# SCH.net
KiCad netlist of a schematic drawn in EasyEDA
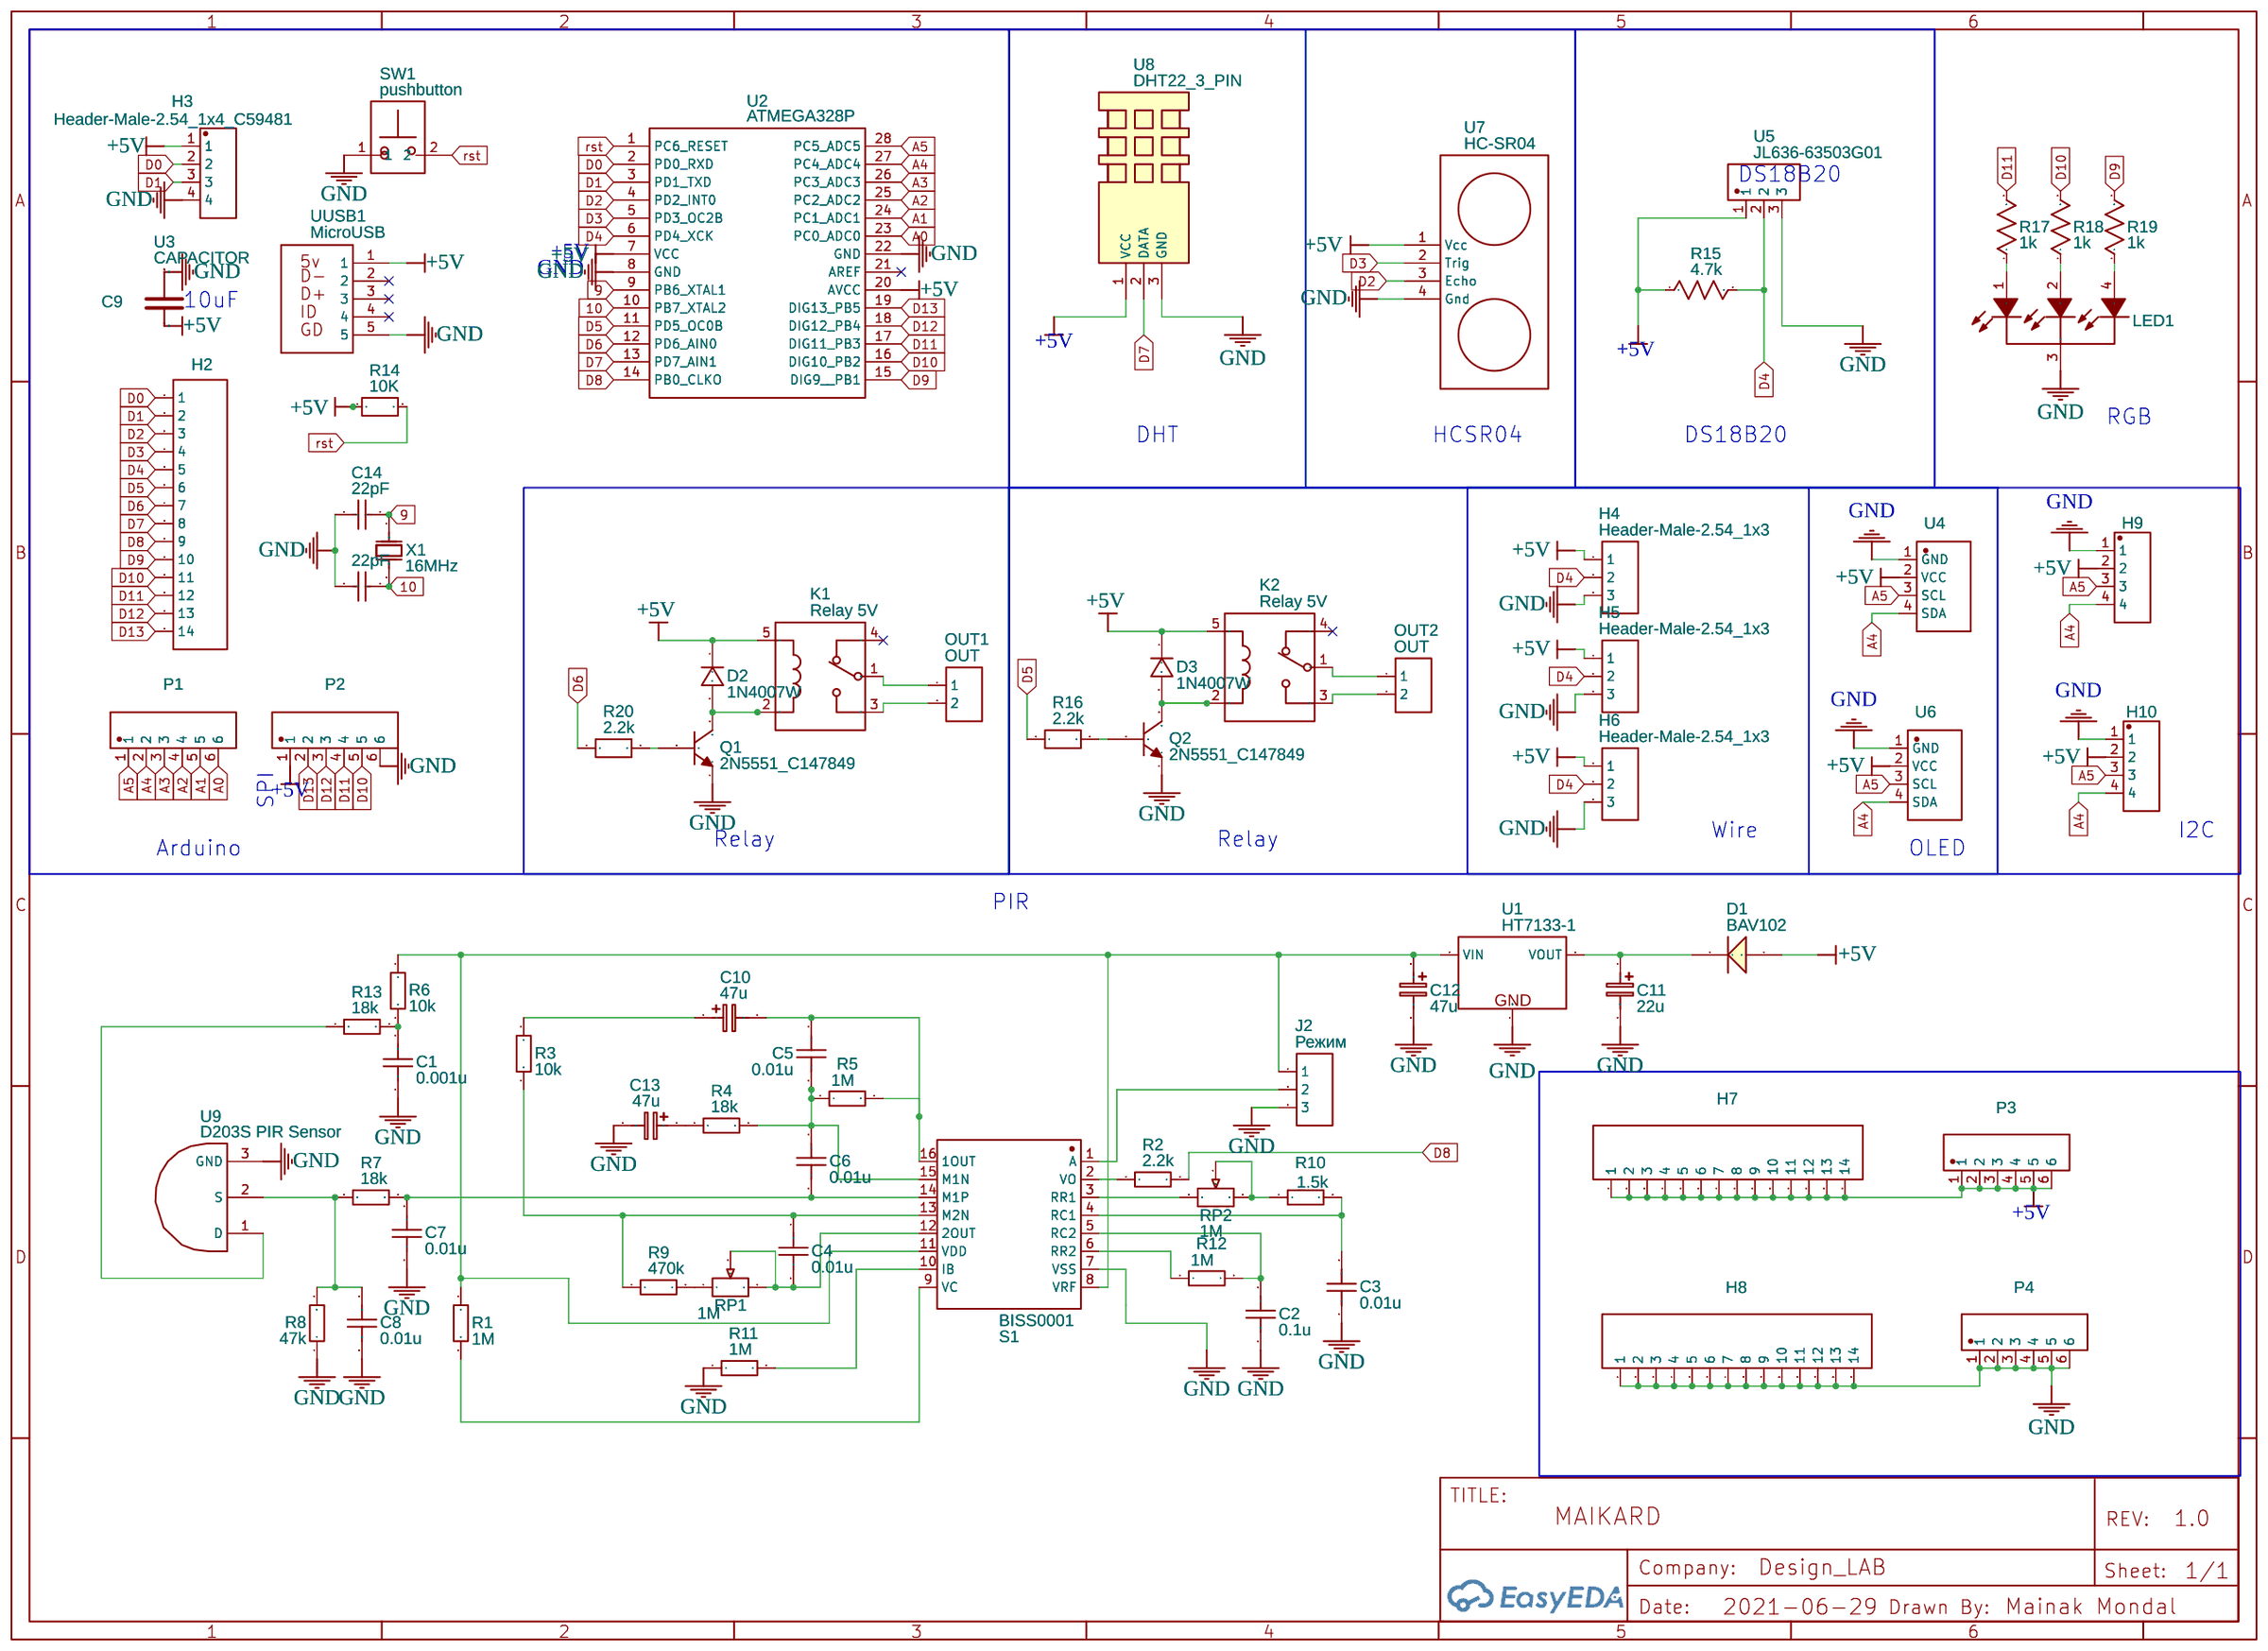
[diagram p0: schematic sheet]

(export (version "E")
  (design (tool "Eeschema 10.0.6"))
  (components
    (comp (ref "C1") (value "0.001u") (libsource (lib "") (part "C_0603_US")))
    (comp (ref "C2") (value "0.1u") (libsource (lib "") (part "C_0603_US_2")))
    (comp (ref "C3") (value "0.01u") (libsource (lib "") (part "C_0603_US")))
    (comp (ref "C4") (value "0.01u") (libsource (lib "") (part "C_0603_US_2")))
    (comp (ref "C5") (value "0.01u") (libsource (lib "") (part "C_0603_US_1")))
    (comp (ref "C6") (value "0.01u") (libsource (lib "") (part "C_0603_US_2")))
    (comp (ref "C7") (value "0.01u") (libsource (lib "") (part "C_0603_US")))
    (comp (ref "C8") (value "0.01u") (libsource (lib "") (part "C_0603_US_2")))
    (comp (ref "C9")
      (value "22pF")
      (fields
        (field (name "BOM_Manufacturer Part") "22pf/50V 10%")
        (field (name "BOM_Supplier Part") "C9316")
      )
      (libsource (lib "") (part "22pF"))
    )
    (comp (ref "C10") (value "47u") (libsource (lib "") (part "CE_TH_D3.0×F1.5_EU")))
    (comp (ref "C11") (value "22u") (libsource (lib "") (part "CE_TH_D3.0×F1.5_EU_2")))
    (comp (ref "C12") (value "47u") (libsource (lib "") (part "CE_TH_D3.0×F1.5_EU_3")))
    (comp (ref "C13") (value "47u") (libsource (lib "") (part "CE_TH_D3.0×F1.5_EU_1")))
    (comp (ref "C14")
      (value "22pF")
      (fields
        (field (name "BOM_Manufacturer Part") "22pf/50V 10%")
        (field (name "BOM_Supplier Part") "C9316")
      )
      (libsource (lib "") (part "22pF"))
    )
    (comp (ref "D1") (value "BAV102") (libsource (lib "") (part "BAV102")))
    (comp (ref "D2")
      (value "1N4007W")
      (fields (field (name "BOM_Supplier Part") "C328592"))
      (libsource (lib "") (part "1N4007W"))
    )
    (comp (ref "D3")
      (value "1N4007W")
      (fields (field (name "BOM_Supplier Part") "C328592"))
      (libsource (lib "") (part "1N4007W"))
    )
    (comp (ref "H2")
      (value "Female header 2.54-1*14P")
      (fields (field (name "BOM_Supplier Part") "C52711"))
      (libsource (lib "") (part "Female header 2.54-1*14P"))
    )
    (comp (ref "H3")
      (value "Header-Male-2.54_1x4_C59481")
      (fields
        (field (name "BOM_Manufacturer Part") "Headers  Pins 1*4P")
        (field (name "BOM_Supplier Part") "C59481")
      )
      (libsource (lib "") (part "Header-Male-2.54_1x4_C59481"))
    )
    (comp (ref "H4")
      (value "Header-Male-2.54_1x3")
      (fields
        (field (name "BOM_Manufacturer Part") "Header2.54mm 1*3P")
        (field (name "BOM_Supplier Part") "C49257")
      )
      (libsource (lib "") (part "Header-Male-2.54_1x3"))
    )
    (comp (ref "H5")
      (value "Header-Male-2.54_1x3")
      (fields
        (field (name "BOM_Manufacturer Part") "Header2.54mm 1*3P")
        (field (name "BOM_Supplier Part") "C49257")
      )
      (libsource (lib "") (part "Header-Male-2.54_1x3"))
    )
    (comp (ref "H6")
      (value "Header-Male-2.54_1x3")
      (fields
        (field (name "BOM_Manufacturer Part") "Header2.54mm 1*3P")
        (field (name "BOM_Supplier Part") "C49257")
      )
      (libsource (lib "") (part "Header-Male-2.54_1x3"))
    )
    (comp (ref "H7")
      (value "Female header 2.54-1*14P")
      (fields (field (name "BOM_Supplier Part") "C52711"))
      (libsource (lib "") (part "Female header 2.54-1*14P_1"))
    )
    (comp (ref "H8")
      (value "Female header 2.54-1*14P")
      (fields (field (name "BOM_Supplier Part") "C52711"))
      (libsource (lib "") (part "Female header 2.54-1*14P_1"))
    )
    (comp (ref "H9")
      (value "Header-Male-2.54_1x4_C59481")
      (fields
        (field (name "BOM_Manufacturer Part") "Headers  Pins 1*4P")
        (field (name "BOM_Supplier Part") "C59481")
      )
      (libsource (lib "") (part "Header-Male-2.54_1x4_C59481"))
    )
    (comp (ref "H10")
      (value "Header-Male-2.54_1x4_C59481")
      (fields
        (field (name "BOM_Manufacturer Part") "Headers  Pins 1*4P")
        (field (name "BOM_Supplier Part") "C59481")
      )
      (libsource (lib "") (part "Header-Male-2.54_1x4_C59481"))
    )
    (comp (ref "J2")
      (value "Режим")
      (fields (field (name "BOM_Supplier Part") "C180248"))
      (libsource (lib "") (part "HDR-M-2.54_1x3"))
    )
    (comp (ref "K1")
      (value "Relay 5V")
      (fields
        (field (name "BOM_Manufacturer Part") "RelayHT3F-12VDC-SHG")
        (field (name "BOM_Supplier Part") "C22022")
      )
      (libsource (lib "") (part "RelayHT3F-12VDC-SHG"))
    )
    (comp (ref "K2")
      (value "Relay 5V")
      (fields
        (field (name "BOM_Manufacturer Part") "RelayHT3F-12VDC-SHG")
        (field (name "BOM_Supplier Part") "C22022")
      )
      (libsource (lib "") (part "RelayHT3F-12VDC-SHG"))
    )
    (comp (ref "LED1")
      (value "RGB LED Common Cathode DIP Package")
      (fields
        (field (name "BOM_Manufacturer Part") "φ5 RGB Transparent LED")
        (field (name "BOM_Supplier Part") "C32985")
      )
      (libsource (lib "") (part "RGB LED Common Cathode DIP Package"))
    )
    (comp (ref "OUT1")
      (value "OUT")
      (fields (field (name "BOM_Supplier Part") "C124375"))
      (libsource (lib "") (part "HDR-M-2.54_1x2"))
    )
    (comp (ref "OUT2")
      (value "OUT")
      (fields (field (name "BOM_Supplier Part") "C124375"))
      (libsource (lib "") (part "HDR-M-2.54_1x2"))
    )
    (comp (ref "P1")
      (value "Header-Female-2.54_1x6")
      (fields
        (field (name "BOM_Manufacturer Part") "Female header 1*6p")
        (field (name "BOM_Supplier Part") "C40877")
      )
      (libsource (lib "") (part "Header-Female-2.54_1x6"))
    )
    (comp (ref "P2")
      (value "Header-Female-2.54_1x6")
      (fields
        (field (name "BOM_Manufacturer Part") "Female header 1*6p")
        (field (name "BOM_Supplier Part") "C40877")
      )
      (libsource (lib "") (part "Header-Female-2.54_1x6"))
    )
    (comp (ref "P3")
      (value "Header-Female-2.54_1x6")
      (fields
        (field (name "BOM_Manufacturer Part") "Female header 1*6p")
        (field (name "BOM_Supplier Part") "C40877")
      )
      (libsource (lib "") (part "Header-Female-2.54_1x6"))
    )
    (comp (ref "P4")
      (value "Header-Female-2.54_1x6")
      (fields
        (field (name "BOM_Manufacturer Part") "Female header 1*6p")
        (field (name "BOM_Supplier Part") "C40877")
      )
      (libsource (lib "") (part "Header-Female-2.54_1x6"))
    )
    (comp (ref "Q1")
      (value "2N5551_C147849")
      (fields (field (name "BOM_Manufacturer Part") "2N5551") (field (name "BOM_Supplier Part") "C147849"))
      (libsource (lib "") (part "2N5551_C147849"))
    )
    (comp (ref "Q2")
      (value "2N5551_C147849")
      (fields (field (name "BOM_Manufacturer Part") "2N5551") (field (name "BOM_Supplier Part") "C147849"))
      (libsource (lib "") (part "2N5551_C147849"))
    )
    (comp (ref "R1")
      (value "1M")
      (fields
        (field (name "BOM_Manufacturer Part") "0.56R(R56) ±1%")
        (field (name "BOM_Supplier Part") "C19772")
      )
      (libsource (lib "") (part "0.56Ω_1"))
    )
    (comp (ref "R2")
      (value "2.2k")
      (fields
        (field (name "BOM_Manufacturer Part") "0.56R(R56) ±1%")
        (field (name "BOM_Supplier Part") "C19772")
      )
      (libsource (lib "") (part "0.56Ω"))
    )
    (comp (ref "R3")
      (value "10k")
      (fields
        (field (name "BOM_Manufacturer Part") "0.56R(R56) ±1%")
        (field (name "BOM_Supplier Part") "C19772")
      )
      (libsource (lib "") (part "0.56Ω_1"))
    )
    (comp (ref "R4")
      (value "18k")
      (fields
        (field (name "BOM_Manufacturer Part") "0.56R(R56) ±1%")
        (field (name "BOM_Supplier Part") "C19772")
      )
      (libsource (lib "") (part "0.56Ω"))
    )
    (comp (ref "R5")
      (value "1M")
      (fields
        (field (name "BOM_Manufacturer Part") "0.56R(R56) ±1%")
        (field (name "BOM_Supplier Part") "C19772")
      )
      (libsource (lib "") (part "0.56Ω"))
    )
    (comp (ref "R6")
      (value "10k")
      (fields
        (field (name "BOM_Manufacturer Part") "0.56R(R56) ±1%")
        (field (name "BOM_Supplier Part") "C19772")
      )
      (libsource (lib "") (part "0.56Ω_1"))
    )
    (comp (ref "R7")
      (value "18k")
      (fields
        (field (name "BOM_Manufacturer Part") "0.56R(R56) ±1%")
        (field (name "BOM_Supplier Part") "C19772")
      )
      (libsource (lib "") (part "0.56Ω"))
    )
    (comp (ref "R8")
      (value "47k")
      (fields
        (field (name "BOM_Manufacturer Part") "0.56R(R56) ±1%")
        (field (name "BOM_Supplier Part") "C19772")
      )
      (libsource (lib "") (part "0.56Ω_2"))
    )
    (comp (ref "R9")
      (value "470k")
      (fields
        (field (name "BOM_Manufacturer Part") "0.56R(R56) ±1%")
        (field (name "BOM_Supplier Part") "C19772")
      )
      (libsource (lib "") (part "0.56Ω"))
    )
    (comp (ref "R10")
      (value "1.5k")
      (fields
        (field (name "BOM_Manufacturer Part") "0.56R(R56) ±1%")
        (field (name "BOM_Supplier Part") "C19772")
      )
      (libsource (lib "") (part "0.56Ω"))
    )
    (comp (ref "R11")
      (value "1M")
      (fields
        (field (name "BOM_Manufacturer Part") "0.56R(R56) ±1%")
        (field (name "BOM_Supplier Part") "C19772")
      )
      (libsource (lib "") (part "0.56Ω"))
    )
    (comp (ref "R12")
      (value "1M")
      (fields
        (field (name "BOM_Manufacturer Part") "0.56R(R56) ±1%")
        (field (name "BOM_Supplier Part") "C19772")
      )
      (libsource (lib "") (part "0.56Ω"))
    )
    (comp (ref "R13")
      (value "18k")
      (fields
        (field (name "BOM_Manufacturer Part") "0.56R(R56) ±1%")
        (field (name "BOM_Supplier Part") "C19772")
      )
      (libsource (lib "") (part "0.56Ω"))
    )
    (comp (ref "R14")
      (value "10K")
      (fields
        (field (name "BOM_Manufacturer Part") "Resistor MF25 10K, 0.25W")
        (field (name "BOM_Supplier Part") "934-1110")
      )
      (libsource (lib "") (part "10K"))
    )
    (comp (ref "R15") (value "4.7k") (libsource (lib "") (part "R_0201_US")))
    (comp (ref "R16") (value "2.2k") (libsource (lib "") (part "R_AXIAL-0.3_EU")))
    (comp (ref "R17") (value "1k") (libsource (lib "") (part "R_0201_US_1")))
    (comp (ref "R18") (value "1k") (libsource (lib "") (part "R_0201_US_1")))
    (comp (ref "R19") (value "1k") (libsource (lib "") (part "R_0201_US_1")))
    (comp (ref "R20") (value "2.2k") (libsource (lib "") (part "R_AXIAL-0.3_EU")))
    (comp (ref "RP1") (value "1M") (libsource (lib "") (part "R_3386P_EU")))
    (comp (ref "RP2") (value "1M") (libsource (lib "") (part "R_3386P_EU")))
    (comp (ref "S1")
      (value "BISS0001")
      (fields (field (name "BOM_Supplier Part") "C82210"))
      (libsource (lib "") (part "BISS0001"))
    )
    (comp (ref "SW1") (value "pushbutton") (libsource (lib "") (part "pushbutton")))
    (comp (ref "U1")
      (value "HT7133-1")
      (fields (field (name "BOM_Supplier Part") "C347181"))
      (libsource (lib "") (part "HT7133-1"))
    )
    (comp (ref "U2")
      (value "ATMEGA328P")
      (fields
        (field (name "BOM_Manufacturer Part") "ATMEGA328P-PU")
        (field (name "BOM_Supplier Part") "C33901")
      )
      (libsource (lib "") (part "ATMEGA328P"))
    )
    (comp (ref "U3") (value "CAPACITOR") (libsource (lib "") (part "CAPACITOR")))
    (comp (ref "U4")
      (value "0.96 128X64 I2C SSD1306 OLED WHITE/BLUE")
      (fields (field (name "BOM_Manufacturer Part") "OLED 4PIN"))
      (libsource (lib "") (part "0.96 128X64 I2C SSD1306 OLED WHITE/BLUE"))
    )
    (comp (ref "U5")
      (value "JL636-63503G01")
      (fields (field (name "BOM_Supplier Part") "C394553"))
      (libsource (lib "") (part "JL636-63503G01"))
    )
    (comp (ref "U6")
      (value "0.96 128X64 I2C SSD1306 OLED WHITE/BLUE")
      (fields (field (name "BOM_Manufacturer Part") "OLED 4PIN"))
      (libsource (lib "") (part "0.96 128X64 I2C SSD1306 OLED WHITE/BLUE"))
    )
    (comp (ref "U7") (value "HC-SR04") (libsource (lib "") (part "HC-SR04")))
    (comp (ref "U8")
      (value "DHT22_3_PIN")
      (fields
        (field (name "BOM_Manufacturer Part") "DHT22")
        (field (name "BOM_Supplier Part") "PRODUCT ID: 385")
      )
      (libsource (lib "") (part "DHT22_3_PIN"))
    )
    (comp (ref "U9")
      (value "D203S PIR Sensor")
      (fields (field (name "BOM_Manufacturer Part") "D203S") (field (name "BOM_Supplier Part") "C78793"))
      (libsource (lib "") (part "D203S PIR Sensor"))
    )
    (comp (ref "UUSB1")
      (value "MicroUSB")
      (fields (field (name "BOM_Manufacturer Part") "Speaker"))
      (libsource (lib "") (part "MicroUSB"))
    )
    (comp (ref "X1")
      (value "16MHz")
      (fields
        (field (name "BOM_Manufacturer Part") "X49SD16MSD2SC")
        (field (name "BOM_Supplier Part") "C16212")
      )
      (libsource (lib "") (part "XTAL16MHZ DIP"))
    )
  )
  (nets
    (net (code "1") (name "+5V") (class "Default")
      (node (ref "D1") (pin "1") (pinfunction "A_1") (pintype "unspecified"))
      (node (ref "D2") (pin "1") (pinfunction "1_1") (pintype "unspecified"))
      (node (ref "D3") (pin "1") (pinfunction "1_1") (pintype "unspecified"))
      (node (ref "H10") (pin "2") (pinfunction "2_2") (pintype "unspecified"))
      (node (ref "H3") (pin "1") (pinfunction "1_1") (pintype "unspecified"))
      (node (ref "H4") (pin "1") (pinfunction "1_1") (pintype "input"))
      (node (ref "H5") (pin "1") (pinfunction "1_1") (pintype "input"))
      (node (ref "H6") (pin "1") (pinfunction "1_1") (pintype "input"))
      (node (ref "H7") (pin "1") (pinfunction "1_1") (pintype "input"))
      (node (ref "H7") (pin "10") (pinfunction "10_10") (pintype "input"))
      (node (ref "H7") (pin "11") (pinfunction "11_11") (pintype "input"))
      (node (ref "H7") (pin "12") (pinfunction "12_12") (pintype "input"))
      (node (ref "H7") (pin "13") (pinfunction "13_13") (pintype "input"))
      (node (ref "H7") (pin "14") (pinfunction "14_14") (pintype "input"))
      (node (ref "H7") (pin "2") (pinfunction "2_2") (pintype "input"))
      (node (ref "H7") (pin "3") (pinfunction "3_3") (pintype "input"))
      (node (ref "H7") (pin "4") (pinfunction "4_4") (pintype "input"))
      (node (ref "H7") (pin "5") (pinfunction "5_5") (pintype "input"))
      (node (ref "H7") (pin "6") (pinfunction "6_6") (pintype "input"))
      (node (ref "H7") (pin "7") (pinfunction "7_7") (pintype "input"))
      (node (ref "H7") (pin "8") (pinfunction "8_8") (pintype "input"))
      (node (ref "H7") (pin "9") (pinfunction "9_9") (pintype "input"))
      (node (ref "H9") (pin "2") (pinfunction "2_2") (pintype "unspecified"))
      (node (ref "K1") (pin "5") (pinfunction "5_5") (pintype "unspecified"))
      (node (ref "K2") (pin "5") (pinfunction "5_5") (pintype "unspecified"))
      (node (ref "P2") (pin "1") (pinfunction "1_1") (pintype "unspecified"))
      (node (ref "P3") (pin "1") (pinfunction "1_1") (pintype "unspecified"))
      (node (ref "P3") (pin "2") (pinfunction "2_2") (pintype "unspecified"))
      (node (ref "P3") (pin "3") (pinfunction "3_3") (pintype "unspecified"))
      (node (ref "P3") (pin "4") (pinfunction "4_4") (pintype "unspecified"))
      (node (ref "P3") (pin "5") (pinfunction "5_5") (pintype "unspecified"))
      (node (ref "P3") (pin "6") (pinfunction "6_6") (pintype "unspecified"))
      (node (ref "R14") (pin "1") (pinfunction "1_1") (pintype "unspecified"))
      (node (ref "R15") (pin "1") (pinfunction "1_1") (pintype "unspecified"))
      (node (ref "U2") (pin "20") (pinfunction "AVCC_20") (pintype "passive"))
      (node (ref "U2") (pin "7") (pinfunction "VCC_7") (pintype "passive"))
      (node (ref "U3") (pin "P$1") (pinfunction "P$1_P$1") (pintype "unspecified"))
      (node (ref "U4") (pin "2") (pinfunction "VCC_2") (pintype "unspecified"))
      (node (ref "U5") (pin "1") (pinfunction "1_1") (pintype "unspecified"))
      (node (ref "U6") (pin "2") (pinfunction "VCC_2") (pintype "unspecified"))
      (node (ref "U7") (pin "1") (pinfunction "Vcc_1") (pintype "unspecified"))
      (node (ref "U8") (pin "1") (pinfunction "VCC_1") (pintype "unspecified"))
      (node (ref "UUSB1") (pin "1") (pinfunction "1_1") (pintype "unspecified"))
    )
    (net (code "2") (name "9") (class "Default")
      (node (ref "C14") (pin "2") (pinfunction "2_2") (pintype "input"))
      (node (ref "U2") (pin "9") (pinfunction "PB6_XTAL1_9") (pintype "bidirectional"))
      (node (ref "X1") (pin "1") (pinfunction "OSC1_1") (pintype "input"))
    )
    (net (code "3") (name "10") (class "Default")
      (node (ref "C9") (pin "2") (pinfunction "2_2") (pintype "input"))
      (node (ref "U2") (pin "10") (pinfunction "PB7_XTAL2_10") (pintype "bidirectional"))
      (node (ref "X1") (pin "2") (pinfunction "OSC2_2") (pintype "input"))
    )
    (net (code "4") (name "A0") (class "Default")
      (node (ref "P1") (pin "6") (pinfunction "6_6") (pintype "unspecified"))
      (node (ref "U2") (pin "23") (pinfunction "PC0_ADC0_23") (pintype "bidirectional"))
    )
    (net (code "5") (name "A1") (class "Default")
      (node (ref "P1") (pin "5") (pinfunction "5_5") (pintype "unspecified"))
      (node (ref "U2") (pin "24") (pinfunction "PC1_ADC1_24") (pintype "bidirectional"))
    )
    (net (code "6") (name "A2") (class "Default")
      (node (ref "P1") (pin "4") (pinfunction "4_4") (pintype "unspecified"))
      (node (ref "U2") (pin "25") (pinfunction "PC2_ADC2_25") (pintype "bidirectional"))
    )
    (net (code "7") (name "A3") (class "Default")
      (node (ref "P1") (pin "3") (pinfunction "3_3") (pintype "unspecified"))
      (node (ref "U2") (pin "26") (pinfunction "PC3_ADC3_26") (pintype "bidirectional"))
    )
    (net (code "8") (name "A4") (class "Default")
      (node (ref "H10") (pin "4") (pinfunction "4_4") (pintype "unspecified"))
      (node (ref "H9") (pin "4") (pinfunction "4_4") (pintype "unspecified"))
      (node (ref "P1") (pin "2") (pinfunction "2_2") (pintype "unspecified"))
      (node (ref "U2") (pin "27") (pinfunction "PC4_ADC4_27") (pintype "bidirectional"))
      (node (ref "U4") (pin "4") (pinfunction "SDA_4") (pintype "unspecified"))
      (node (ref "U6") (pin "4") (pinfunction "SDA_4") (pintype "unspecified"))
    )
    (net (code "9") (name "A5") (class "Default")
      (node (ref "H10") (pin "3") (pinfunction "3_3") (pintype "unspecified"))
      (node (ref "H9") (pin "3") (pinfunction "3_3") (pintype "unspecified"))
      (node (ref "P1") (pin "1") (pinfunction "1_1") (pintype "unspecified"))
      (node (ref "U2") (pin "28") (pinfunction "PC5_ADC5_28") (pintype "bidirectional"))
      (node (ref "U4") (pin "3") (pinfunction "SCL_3") (pintype "unspecified"))
      (node (ref "U6") (pin "3") (pinfunction "SCL_3") (pintype "unspecified"))
    )
    (net (code "10") (name "D0") (class "Default")
      (node (ref "H2") (pin "1") (pinfunction "1_1") (pintype "input"))
      (node (ref "H3") (pin "2") (pinfunction "2_2") (pintype "unspecified"))
      (node (ref "U2") (pin "2") (pinfunction "PD0_RXD_2") (pintype "bidirectional"))
    )
    (net (code "11") (name "D1") (class "Default")
      (node (ref "H2") (pin "2") (pinfunction "2_2") (pintype "input"))
      (node (ref "H3") (pin "3") (pinfunction "3_3") (pintype "unspecified"))
      (node (ref "U2") (pin "3") (pinfunction "PD1_TXD_3") (pintype "bidirectional"))
    )
    (net (code "12") (name "D2") (class "Default")
      (node (ref "H2") (pin "3") (pinfunction "3_3") (pintype "input"))
      (node (ref "U2") (pin "4") (pinfunction "PD2_INT0_4") (pintype "bidirectional"))
      (node (ref "U7") (pin "3") (pinfunction "Echo_3") (pintype "unspecified"))
    )
    (net (code "13") (name "D3") (class "Default")
      (node (ref "H2") (pin "4") (pinfunction "4_4") (pintype "input"))
      (node (ref "U2") (pin "5") (pinfunction "PD3_OC2B_5") (pintype "bidirectional"))
      (node (ref "U7") (pin "2") (pinfunction "Trig_2") (pintype "unspecified"))
    )
    (net (code "14") (name "D4") (class "Default")
      (node (ref "H2") (pin "5") (pinfunction "5_5") (pintype "input"))
      (node (ref "H4") (pin "2") (pinfunction "2_2") (pintype "input"))
      (node (ref "H5") (pin "2") (pinfunction "2_2") (pintype "input"))
      (node (ref "H6") (pin "2") (pinfunction "2_2") (pintype "input"))
      (node (ref "R15") (pin "2") (pinfunction "2_2") (pintype "unspecified"))
      (node (ref "U2") (pin "6") (pinfunction "PD4_XCK_6") (pintype "bidirectional"))
      (node (ref "U5") (pin "2") (pinfunction "2_2") (pintype "unspecified"))
    )
    (net (code "15") (name "D5") (class "Default")
      (node (ref "H2") (pin "6") (pinfunction "6_6") (pintype "input"))
      (node (ref "R16") (pin "1") (pinfunction "1_1") (pintype "unspecified"))
      (node (ref "U2") (pin "11") (pinfunction "PD5_OC0B_11") (pintype "bidirectional"))
    )
    (net (code "16") (name "D6") (class "Default")
      (node (ref "H2") (pin "7") (pinfunction "7_7") (pintype "input"))
      (node (ref "R20") (pin "1") (pinfunction "1_1") (pintype "unspecified"))
      (node (ref "U2") (pin "12") (pinfunction "PD6_AIN0_12") (pintype "bidirectional"))
    )
    (net (code "17") (name "D7") (class "Default")
      (node (ref "H2") (pin "8") (pinfunction "8_8") (pintype "input"))
      (node (ref "U2") (pin "13") (pinfunction "PD7_AIN1_13") (pintype "bidirectional"))
      (node (ref "U8") (pin "2") (pinfunction "DATA_2") (pintype "unspecified"))
    )
    (net (code "18") (name "D8") (class "Default")
      (node (ref "H2") (pin "9") (pinfunction "9_9") (pintype "input"))
      (node (ref "R2") (pin "2") (pinfunction "2_2") (pintype "input"))
      (node (ref "U2") (pin "14") (pinfunction "PB0_CLKO_14") (pintype "bidirectional"))
    )
    (net (code "19") (name "D9") (class "Default")
      (node (ref "H2") (pin "10") (pinfunction "10_10") (pintype "input"))
      (node (ref "R19") (pin "2") (pinfunction "2_2") (pintype "unspecified"))
      (node (ref "U2") (pin "15") (pinfunction "DIG9__PB1_15") (pintype "bidirectional"))
    )
    (net (code "20") (name "D10") (class "Default")
      (node (ref "H2") (pin "11") (pinfunction "11_11") (pintype "input"))
      (node (ref "P2") (pin "5") (pinfunction "5_5") (pintype "unspecified"))
      (node (ref "R18") (pin "2") (pinfunction "2_2") (pintype "unspecified"))
      (node (ref "U2") (pin "16") (pinfunction "DIG10_PB2_16") (pintype "bidirectional"))
    )
    (net (code "21") (name "D11") (class "Default")
      (node (ref "H2") (pin "12") (pinfunction "12_12") (pintype "input"))
      (node (ref "P2") (pin "4") (pinfunction "4_4") (pintype "unspecified"))
      (node (ref "R17") (pin "2") (pinfunction "2_2") (pintype "unspecified"))
      (node (ref "U2") (pin "17") (pinfunction "DIG11_PB3_17") (pintype "bidirectional"))
    )
    (net (code "22") (name "D12") (class "Default")
      (node (ref "H2") (pin "13") (pinfunction "13_13") (pintype "input"))
      (node (ref "P2") (pin "3") (pinfunction "3_3") (pintype "unspecified"))
      (node (ref "U2") (pin "18") (pinfunction "DIG12_PB4_18") (pintype "bidirectional"))
    )
    (net (code "23") (name "D13") (class "Default")
      (node (ref "H2") (pin "14") (pinfunction "14_14") (pintype "input"))
      (node (ref "P2") (pin "2") (pinfunction "2_2") (pintype "unspecified"))
      (node (ref "U2") (pin "19") (pinfunction "DIG13_PB5_19") (pintype "bidirectional"))
    )
    (net (code "24") (name "GND") (class "Default")
      (node (ref "C1") (pin "1") (pinfunction "1_1") (pintype "unspecified"))
      (node (ref "C11") (pin "2") (pinfunction "2_2") (pintype "unspecified"))
      (node (ref "C12") (pin "2") (pinfunction "2_2") (pintype "unspecified"))
      (node (ref "C13") (pin "2") (pinfunction "2_2") (pintype "unspecified"))
      (node (ref "C14") (pin "1") (pinfunction "1_1") (pintype "input"))
      (node (ref "C2") (pin "2") (pinfunction "2_2") (pintype "unspecified"))
      (node (ref "C3") (pin "1") (pinfunction "1_1") (pintype "unspecified"))
      (node (ref "C7") (pin "1") (pinfunction "1_1") (pintype "unspecified"))
      (node (ref "C8") (pin "2") (pinfunction "2_2") (pintype "unspecified"))
      (node (ref "C9") (pin "1") (pinfunction "1_1") (pintype "input"))
      (node (ref "H10") (pin "1") (pinfunction "1_1") (pintype "unspecified"))
      (node (ref "H3") (pin "4") (pinfunction "4_4") (pintype "unspecified"))
      (node (ref "H4") (pin "3") (pinfunction "3_3") (pintype "input"))
      (node (ref "H5") (pin "3") (pinfunction "3_3") (pintype "input"))
      (node (ref "H6") (pin "3") (pinfunction "3_3") (pintype "input"))
      (node (ref "H8") (pin "1") (pinfunction "1_1") (pintype "input"))
      (node (ref "H8") (pin "10") (pinfunction "10_10") (pintype "input"))
      (node (ref "H8") (pin "11") (pinfunction "11_11") (pintype "input"))
      (node (ref "H8") (pin "12") (pinfunction "12_12") (pintype "input"))
      (node (ref "H8") (pin "13") (pinfunction "13_13") (pintype "input"))
      (node (ref "H8") (pin "14") (pinfunction "14_14") (pintype "input"))
      (node (ref "H8") (pin "2") (pinfunction "2_2") (pintype "input"))
      (node (ref "H8") (pin "3") (pinfunction "3_3") (pintype "input"))
      (node (ref "H8") (pin "4") (pinfunction "4_4") (pintype "input"))
      (node (ref "H8") (pin "5") (pinfunction "5_5") (pintype "input"))
      (node (ref "H8") (pin "6") (pinfunction "6_6") (pintype "input"))
      (node (ref "H8") (pin "7") (pinfunction "7_7") (pintype "input"))
      (node (ref "H8") (pin "8") (pinfunction "8_8") (pintype "input"))
      (node (ref "H8") (pin "9") (pinfunction "9_9") (pintype "input"))
      (node (ref "H9") (pin "1") (pinfunction "1_1") (pintype "unspecified"))
      (node (ref "J2") (pin "3") (pinfunction "3_3") (pintype "input"))
      (node (ref "LED1") (pin "3") (pinfunction "A_3") (pintype "unspecified"))
      (node (ref "P2") (pin "6") (pinfunction "6_6") (pintype "unspecified"))
      (node (ref "P4") (pin "1") (pinfunction "1_1") (pintype "unspecified"))
      (node (ref "P4") (pin "2") (pinfunction "2_2") (pintype "unspecified"))
      (node (ref "P4") (pin "3") (pinfunction "3_3") (pintype "unspecified"))
      (node (ref "P4") (pin "4") (pinfunction "4_4") (pintype "unspecified"))
      (node (ref "P4") (pin "5") (pinfunction "5_5") (pintype "unspecified"))
      (node (ref "P4") (pin "6") (pinfunction "6_6") (pintype "unspecified"))
      (node (ref "Q1") (pin "1") (pinfunction "E_1") (pintype "unspecified"))
      (node (ref "Q2") (pin "1") (pinfunction "E_1") (pintype "unspecified"))
      (node (ref "R11") (pin "1") (pinfunction "1_1") (pintype "input"))
      (node (ref "R8") (pin "1") (pinfunction "1_1") (pintype "input"))
      (node (ref "S1") (pin "7") (pinfunction "VSS_7") (pintype "unspecified"))
      (node (ref "SW1") (pin "1") (pinfunction "1_1") (pintype "unspecified"))
      (node (ref "U1") (pin "1") (pinfunction "GND_1") (pintype "unspecified"))
      (node (ref "U2") (pin "22") (pinfunction "GND_22") (pintype "passive"))
      (node (ref "U2") (pin "8") (pinfunction "GND_8") (pintype "passive"))
      (node (ref "U3") (pin "P$2") (pinfunction "P$2_P$2") (pintype "unspecified"))
      (node (ref "U4") (pin "1") (pinfunction "GND_1") (pintype "unspecified"))
      (node (ref "U5") (pin "3") (pinfunction "3_3") (pintype "unspecified"))
      (node (ref "U6") (pin "1") (pinfunction "GND_1") (pintype "unspecified"))
      (node (ref "U7") (pin "4") (pinfunction "Gnd_4") (pintype "unspecified"))
      (node (ref "U8") (pin "3") (pinfunction "GND_3") (pintype "unspecified"))
      (node (ref "U9") (pin "3") (pinfunction "GND_3") (pintype "unspecified"))
      (node (ref "UUSB1") (pin "5") (pinfunction "5_5") (pintype "unspecified"))
    )
    (net (code "25") (name "Net-(C1-Pad2)") (class "Default")
      (node (ref "C1") (pin "2") (pinfunction "2_2") (pintype "unspecified"))
      (node (ref "R13") (pin "2") (pinfunction "2_2") (pintype "input"))
      (node (ref "R6") (pin "2") (pinfunction "2_2") (pintype "input"))
    )
    (net (code "26") (name "Net-(C10-Pad1)") (class "Default")
      (node (ref "C10") (pin "1") (pinfunction "1_1") (pintype "unspecified"))
      (node (ref "R3") (pin "1") (pinfunction "1_1") (pintype "input"))
    )
    (net (code "27") (name "Net-(C13-Pad1)") (class "Default")
      (node (ref "C13") (pin "1") (pinfunction "1_1") (pintype "unspecified"))
      (node (ref "R4") (pin "1") (pinfunction "1_1") (pintype "input"))
    )
    (net (code "28") (name "Net-(D1-K)") (class "Default")
      (node (ref "C11") (pin "1") (pinfunction "1_1") (pintype "unspecified"))
      (node (ref "D1") (pin "2") (pinfunction "K_2") (pintype "unspecified"))
      (node (ref "U1") (pin "3") (pinfunction "VOUT_3") (pintype "unspecified"))
    )
    (net (code "29") (name "Net-(K1-Pad1)") (class "Default")
      (node (ref "K1") (pin "1") (pinfunction "1_1") (pintype "unspecified"))
      (node (ref "OUT1") (pin "1") (pinfunction "1_1") (pintype "unspecified"))
    )
    (net (code "30") (name "Net-(K1-Pad3)") (class "Default")
      (node (ref "K1") (pin "3") (pinfunction "3_3") (pintype "unspecified"))
      (node (ref "OUT1") (pin "2") (pinfunction "2_2") (pintype "unspecified"))
    )
    (net (code "31") (name "Net-(K2-Pad1)") (class "Default")
      (node (ref "K2") (pin "1") (pinfunction "1_1") (pintype "unspecified"))
      (node (ref "OUT2") (pin "1") (pinfunction "1_1") (pintype "unspecified"))
    )
    (net (code "32") (name "Net-(K2-Pad3)") (class "Default")
      (node (ref "K2") (pin "3") (pinfunction "3_3") (pintype "unspecified"))
      (node (ref "OUT2") (pin "2") (pinfunction "2_2") (pintype "unspecified"))
    )
    (net (code "33") (name "Net-(LED1-K-Pad1)") (class "Default")
      (node (ref "LED1") (pin "1") (pinfunction "K_1") (pintype "unspecified"))
      (node (ref "R17") (pin "1") (pinfunction "1_1") (pintype "unspecified"))
    )
    (net (code "34") (name "Net-(LED1-K-Pad2)") (class "Default")
      (node (ref "LED1") (pin "2") (pinfunction "K_2") (pintype "unspecified"))
      (node (ref "R18") (pin "1") (pinfunction "1_1") (pintype "unspecified"))
    )
    (net (code "35") (name "Net-(LED1-K-Pad4)") (class "Default")
      (node (ref "LED1") (pin "4") (pinfunction "K_4") (pintype "unspecified"))
      (node (ref "R19") (pin "1") (pinfunction "1_1") (pintype "unspecified"))
    )
    (net (code "36") (name "Net-(Q1-B)") (class "Default")
      (node (ref "Q1") (pin "2") (pinfunction "B_2") (pintype "unspecified"))
      (node (ref "R20") (pin "2") (pinfunction "2_2") (pintype "unspecified"))
    )
    (net (code "37") (name "Net-(Q1-C)") (class "Default")
      (node (ref "D2") (pin "2") (pinfunction "2_2") (pintype "unspecified"))
      (node (ref "K1") (pin "2") (pinfunction "2_2") (pintype "unspecified"))
      (node (ref "Q1") (pin "3") (pinfunction "C_3") (pintype "unspecified"))
    )
    (net (code "38") (name "Net-(Q2-B)") (class "Default")
      (node (ref "Q2") (pin "2") (pinfunction "B_2") (pintype "unspecified"))
      (node (ref "R16") (pin "2") (pinfunction "2_2") (pintype "unspecified"))
    )
    (net (code "39") (name "Net-(Q2-C)") (class "Default")
      (node (ref "D3") (pin "2") (pinfunction "2_2") (pintype "unspecified"))
      (node (ref "K2") (pin "2") (pinfunction "2_2") (pintype "unspecified"))
      (node (ref "Q2") (pin "3") (pinfunction "C_3") (pintype "unspecified"))
    )
    (net (code "40") (name "Net-(R9-Pad2)") (class "Default")
      (node (ref "R9") (pin "2") (pinfunction "2_2") (pintype "input"))
      (node (ref "RP1") (pin "1") (pinfunction "1_1") (pintype "input"))
    )
    (net (code "41") (name "Net-(R10-Pad1)") (class "Default")
      (node (ref "R10") (pin "1") (pinfunction "1_1") (pintype "input"))
      (node (ref "RP2") (pin "2") (pinfunction "2_2") (pintype "input"))
      (node (ref "RP2") (pin "3") (pinfunction "3_3") (pintype "input"))
    )
    (net (code "42") (name "Net-(S1-1OUT)") (class "Default")
      (node (ref "C10") (pin "2") (pinfunction "2_2") (pintype "unspecified"))
      (node (ref "C5") (pin "1") (pinfunction "1_1") (pintype "unspecified"))
      (node (ref "R5") (pin "2") (pinfunction "2_2") (pintype "input"))
      (node (ref "S1") (pin "16") (pinfunction "1OUT_16") (pintype "unspecified"))
    )
    (net (code "43") (name "Net-(S1-2OUT)") (class "Default")
      (node (ref "C4") (pin "2") (pinfunction "2_2") (pintype "unspecified"))
      (node (ref "RP1") (pin "2") (pinfunction "2_2") (pintype "input"))
      (node (ref "RP1") (pin "3") (pinfunction "3_3") (pintype "input"))
      (node (ref "S1") (pin "12") (pinfunction "2OUT_12") (pintype "unspecified"))
    )
    (net (code "44") (name "Net-(S1-A)") (class "Default")
      (node (ref "J2") (pin "2") (pinfunction "2_2") (pintype "input"))
      (node (ref "S1") (pin "1") (pinfunction "A_1") (pintype "unspecified"))
    )
    (net (code "45") (name "Net-(S1-IB)") (class "Default")
      (node (ref "R11") (pin "2") (pinfunction "2_2") (pintype "input"))
      (node (ref "S1") (pin "10") (pinfunction "IB_10") (pintype "unspecified"))
    )
    (net (code "46") (name "Net-(S1-M1N)") (class "Default")
      (node (ref "C5") (pin "2") (pinfunction "2_2") (pintype "unspecified"))
      (node (ref "C6") (pin "1") (pinfunction "1_1") (pintype "unspecified"))
      (node (ref "R4") (pin "2") (pinfunction "2_2") (pintype "input"))
      (node (ref "R5") (pin "1") (pinfunction "1_1") (pintype "input"))
      (node (ref "S1") (pin "15") (pinfunction "M1N_15") (pintype "unspecified"))
    )
    (net (code "47") (name "Net-(S1-M1P)") (class "Default")
      (node (ref "C6") (pin "2") (pinfunction "2_2") (pintype "unspecified"))
      (node (ref "C7") (pin "2") (pinfunction "2_2") (pintype "unspecified"))
      (node (ref "R7") (pin "2") (pinfunction "2_2") (pintype "input"))
      (node (ref "S1") (pin "14") (pinfunction "M1P_14") (pintype "unspecified"))
    )
    (net (code "48") (name "Net-(S1-M2N)") (class "Default")
      (node (ref "C4") (pin "1") (pinfunction "1_1") (pintype "unspecified"))
      (node (ref "R3") (pin "2") (pinfunction "2_2") (pintype "input"))
      (node (ref "R9") (pin "1") (pinfunction "1_1") (pintype "input"))
      (node (ref "S1") (pin "13") (pinfunction "M2N_13") (pintype "unspecified"))
    )
    (net (code "49") (name "Net-(S1-RC1)") (class "Default")
      (node (ref "C3") (pin "2") (pinfunction "2_2") (pintype "unspecified"))
      (node (ref "R10") (pin "2") (pinfunction "2_2") (pintype "input"))
      (node (ref "S1") (pin "4") (pinfunction "RC1_4") (pintype "unspecified"))
    )
    (net (code "50") (name "Net-(S1-RC2)") (class "Default")
      (node (ref "C2") (pin "1") (pinfunction "1_1") (pintype "unspecified"))
      (node (ref "R12") (pin "2") (pinfunction "2_2") (pintype "input"))
      (node (ref "S1") (pin "5") (pinfunction "RC2_5") (pintype "unspecified"))
    )
    (net (code "51") (name "Net-(S1-RR1)") (class "Default")
      (node (ref "RP2") (pin "1") (pinfunction "1_1") (pintype "input"))
      (node (ref "S1") (pin "3") (pinfunction "RR1_3") (pintype "unspecified"))
    )
    (net (code "52") (name "Net-(S1-RR2)") (class "Default")
      (node (ref "R12") (pin "1") (pinfunction "1_1") (pintype "input"))
      (node (ref "S1") (pin "6") (pinfunction "RR2_6") (pintype "unspecified"))
    )
    (net (code "53") (name "Net-(S1-VC)") (class "Default")
      (node (ref "R1") (pin "2") (pinfunction "2_2") (pintype "input"))
      (node (ref "S1") (pin "9") (pinfunction "VC_9") (pintype "unspecified"))
    )
    (net (code "54") (name "Net-(S1-VDD)") (class "Default")
      (node (ref "C12") (pin "1") (pinfunction "1_1") (pintype "unspecified"))
      (node (ref "J2") (pin "1") (pinfunction "1_1") (pintype "input"))
      (node (ref "R1") (pin "1") (pinfunction "1_1") (pintype "input"))
      (node (ref "R6") (pin "1") (pinfunction "1_1") (pintype "input"))
      (node (ref "S1") (pin "11") (pinfunction "VDD_11") (pintype "unspecified"))
      (node (ref "S1") (pin "8") (pinfunction "VRF_8") (pintype "unspecified"))
      (node (ref "U1") (pin "2") (pinfunction "VIN_2") (pintype "unspecified"))
    )
    (net (code "55") (name "Net-(S1-VO)") (class "Default")
      (node (ref "R2") (pin "1") (pinfunction "1_1") (pintype "input"))
      (node (ref "S1") (pin "2") (pinfunction "VO_2") (pintype "unspecified"))
    )
    (net (code "56") (name "Net-(U9-D)") (class "Default")
      (node (ref "R13") (pin "1") (pinfunction "1_1") (pintype "input"))
      (node (ref "U9") (pin "1") (pinfunction "D_1") (pintype "unspecified"))
    )
    (net (code "57") (name "Net-(U9-S)") (class "Default")
      (node (ref "C8") (pin "1") (pinfunction "1_1") (pintype "unspecified"))
      (node (ref "R7") (pin "1") (pinfunction "1_1") (pintype "input"))
      (node (ref "R8") (pin "2") (pinfunction "2_2") (pintype "input"))
      (node (ref "U9") (pin "2") (pinfunction "S_2") (pintype "unspecified"))
    )
    (net (code "58") (name "rst") (class "Default")
      (node (ref "R14") (pin "2") (pinfunction "2_2") (pintype "unspecified"))
      (node (ref "SW1") (pin "2") (pinfunction "2_2") (pintype "unspecified"))
      (node (ref "U2") (pin "1") (pinfunction "PC6_RESET_1") (pintype "bidirectional"))
    )
    (net (code "59") (name "unconnected-(K1-Pad4)") (class "Default")
      (node (ref "K1") (pin "4") (pinfunction "4_4") (pintype "unspecified+no_connect"))
    )
    (net (code "60") (name "unconnected-(K2-Pad4)") (class "Default")
      (node (ref "K2") (pin "4") (pinfunction "4_4") (pintype "unspecified+no_connect"))
    )
    (net (code "61") (name "unconnected-(U2-AREF-Pad21)") (class "Default")
      (node (ref "U2") (pin "21") (pinfunction "AREF_21") (pintype "passive+no_connect"))
    )
    (net (code "62") (name "unconnected-(UUSB1-Pad2)") (class "Default")
      (node (ref "UUSB1") (pin "2") (pinfunction "2_2") (pintype "unspecified+no_connect"))
    )
    (net (code "63") (name "unconnected-(UUSB1-Pad3)") (class "Default")
      (node (ref "UUSB1") (pin "3") (pinfunction "3_3") (pintype "unspecified+no_connect"))
    )
    (net (code "64") (name "unconnected-(UUSB1-Pad4)") (class "Default")
      (node (ref "UUSB1") (pin "4") (pinfunction "4_4") (pintype "unspecified+no_connect"))
    )
  )
)
